# Puzzle_Vibrator_v1_0.net
KiCad netlist of a schematic drawn in EAGLE
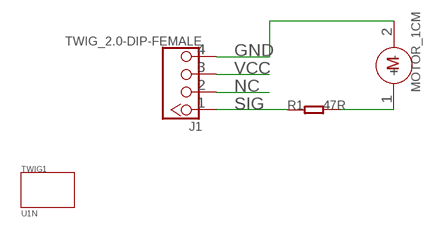
[diagram p0: schematic, sheet 1]

(export (version "E")
  (design (tool "Eeschema 10.0.6"))
  (components
    (comp (ref "J1")
      (value "TWIG_2.0-DIP-FEMALE")
      (footprint "eagle-import:2.0_1X4")
      (libsource (lib "eagle-import") (part "TWIG_2.0-DIP-FEMALE"))
    )
    (comp (ref "M1")
      (value "MOTOR_1CM")
      (footprint "eagle-import:MOTOR_1CM")
      (libsource (lib "eagle-import") (part "MOTOR_1CM"))
    )
    (comp (ref "R1")
      (value "47R")
      (footprint "eagle-import:0603_S")
      (libsource (lib "eagle-import") (part "005-R0603_S"))
    )
    (comp (ref "TWIG1")
      (value "U1N")
      (footprint "eagle-import:U1N")
      (libsource (lib "eagle-import") (part "U1N"))
    )
  )
  (nets
    (net (code "1") (name "/GND") (class "Default")
      (node (ref "J1") (pin "4") (pinfunction "4_4") (pintype "bidirectional"))
      (node (ref "M1") (pin "2") (pinfunction "-_2") (pintype "bidirectional"))
    )
    (net (code "2") (name "/NC") (class "Default")
      (node (ref "J1") (pin "2") (pinfunction "2_2") (pintype "bidirectional"))
    )
    (net (code "3") (name "/SIG") (class "Default")
      (node (ref "J1") (pin "1") (pinfunction "1_1") (pintype "bidirectional"))
      (node (ref "R1") (pin "1") (pinfunction "1_1") (pintype "passive"))
    )
    (net (code "4") (name "/VCC") (class "Default")
      (node (ref "J1") (pin "3") (pinfunction "3_3") (pintype "bidirectional"))
    )
    (net (code "5") (name "Net-(M1-+)") (class "Default")
      (node (ref "M1") (pin "1") (pinfunction "+_1") (pintype "bidirectional"))
      (node (ref "R1") (pin "2") (pinfunction "2_2") (pintype "passive"))
    )
  )
)
